# Merge_ESC_Board.net
KiCad netlist of a schematic drawn in Altium Designer
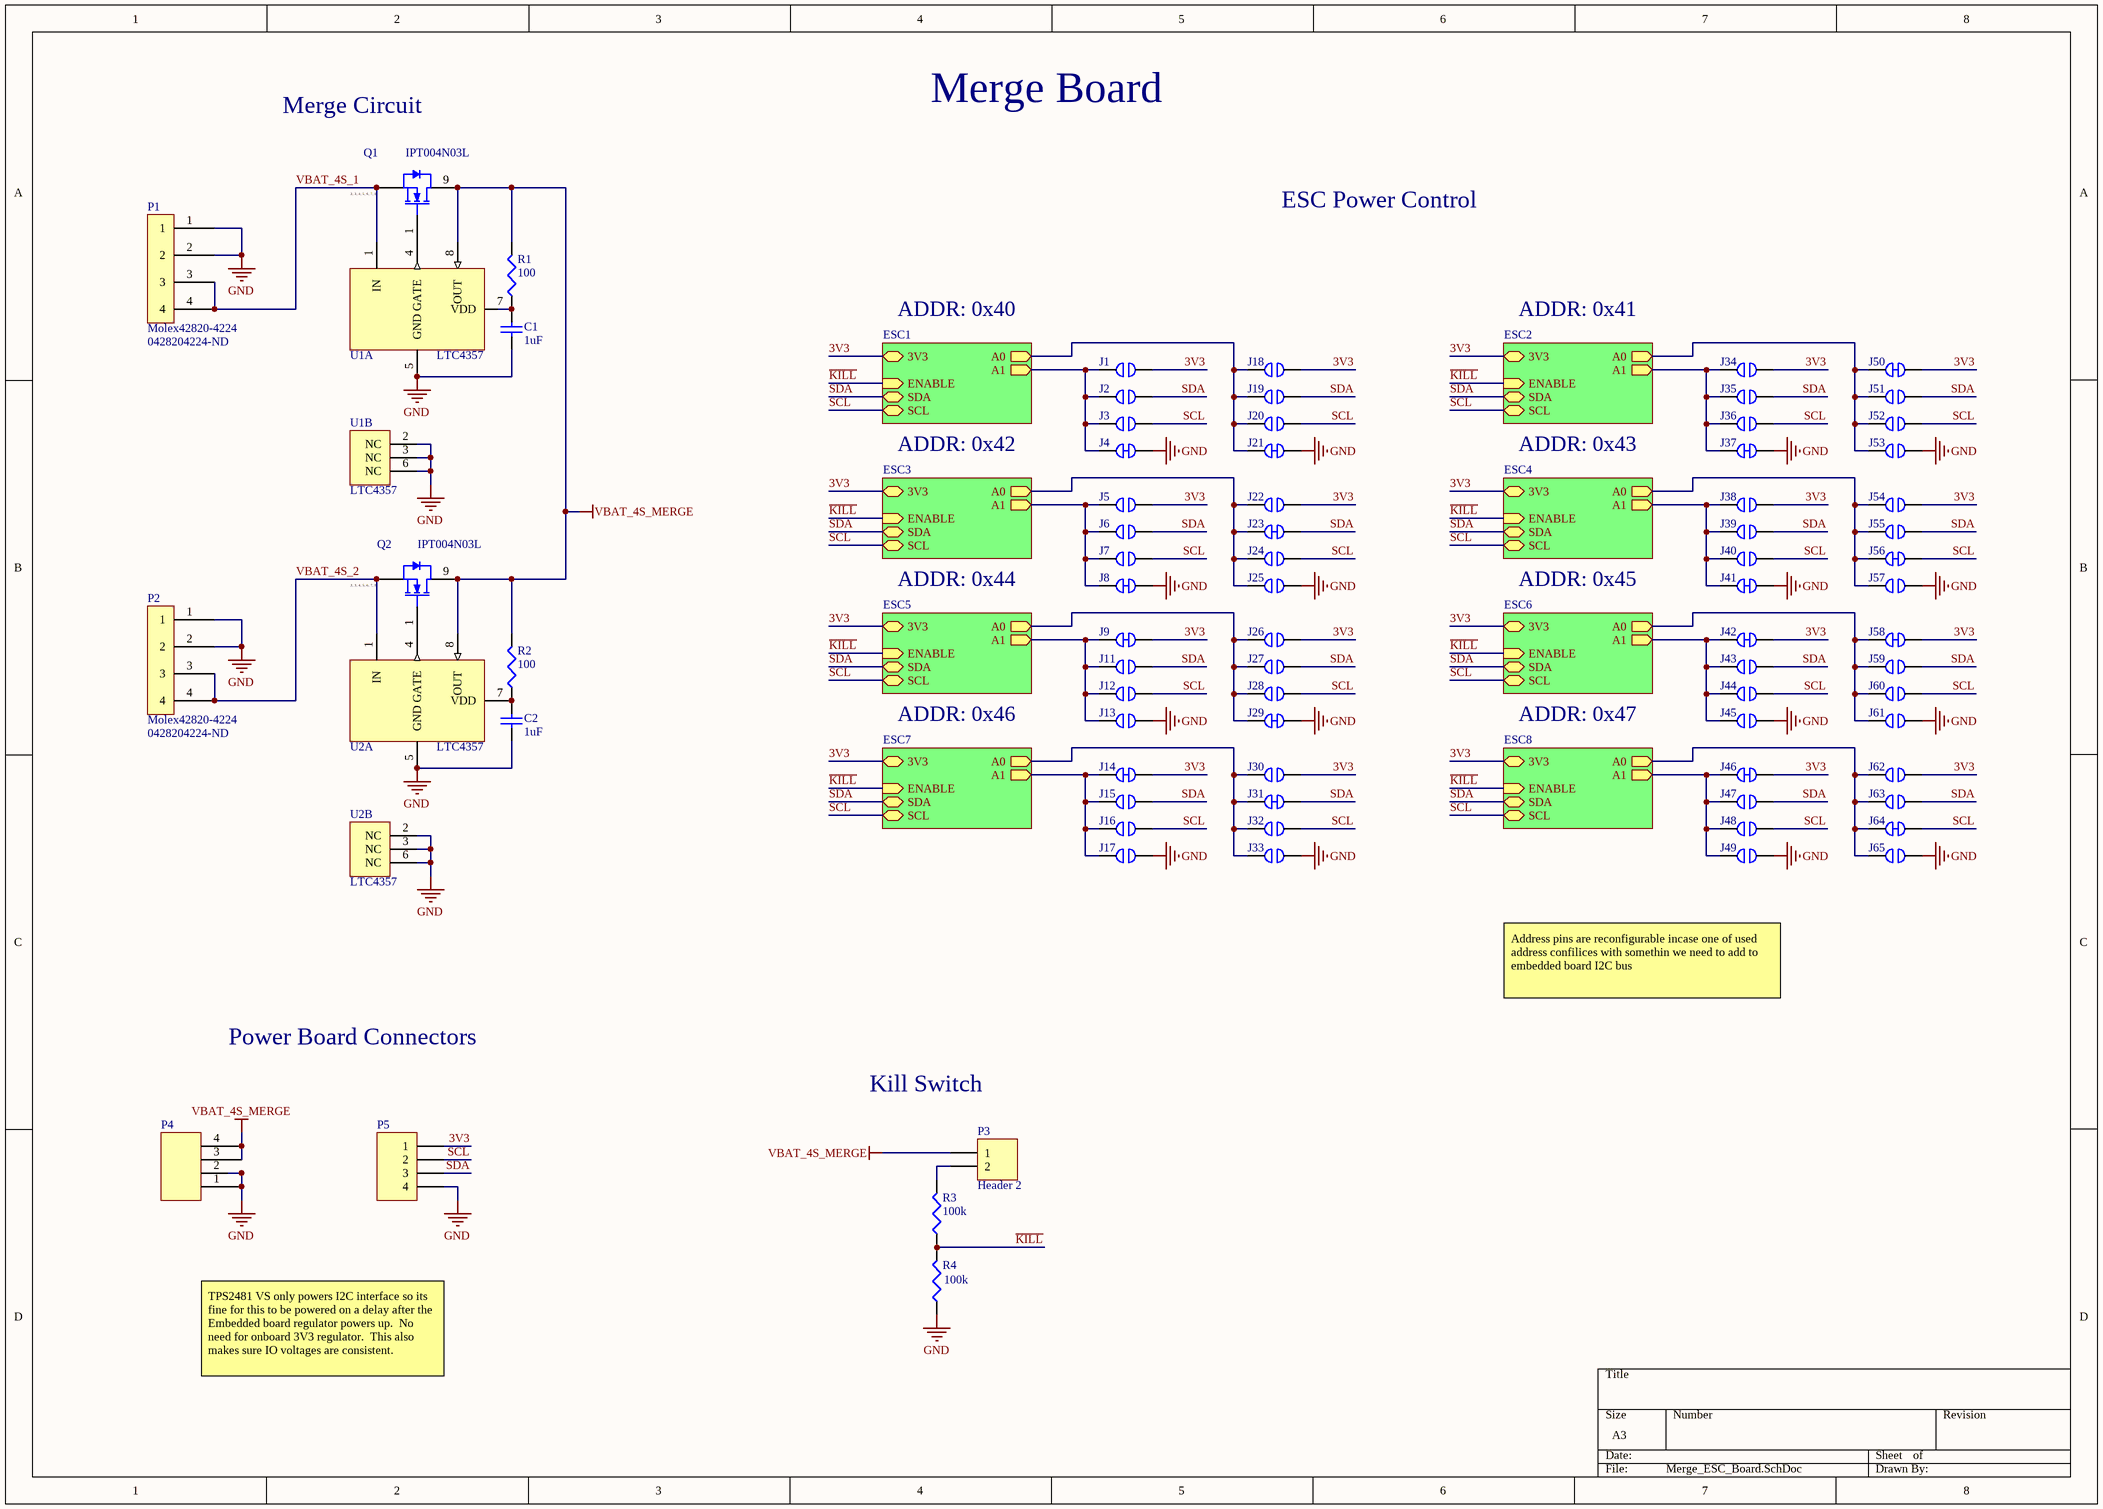
[diagram p0: Merge_ESC_Board.SchDoc]

(export (version "E")
  (design (tool "Eeschema 10.0.6"))
  (components
    (comp (ref "C1")
      (value "1uF")
      (footprint "C1206")
      (description "Capacitor (Semiconductor SIM Model)")
      (fields (field (name "Comment") "Cap Semi") (field (name "PUBLISHER") "Altium Limited"))
      (libsource (lib "Miscellaneous Devices") (part "Cap Semi"))
    )
    (comp (ref "C2")
      (value "1uF")
      (footprint "C1206")
      (description "Capacitor (Semiconductor SIM Model)")
      (fields (field (name "Comment") "Cap Semi") (field (name "PUBLISHER") "Altium Limited"))
      (libsource (lib "Miscellaneous Devices") (part "Cap Semi"))
    )
    (comp (ref "J1")
      (value "JumperOpen")
      (footprint "JUMPER_OPEN")
      (description "Jumper (Default Open)")
      (libsource (lib "Merge_ESC_Board_Library") (part "JumperOpen"))
    )
    (comp (ref "J2")
      (value "JumperOpen")
      (footprint "JUMPER_OPEN")
      (description "Jumper (Default Open)")
      (libsource (lib "Merge_ESC_Board_Library") (part "JumperOpen"))
    )
    (comp (ref "J3")
      (value "JumperOpen")
      (footprint "JUMPER_OPEN")
      (description "Jumper (Default Open)")
      (libsource (lib "Merge_ESC_Board_Library") (part "JumperOpen"))
    )
    (comp (ref "J4")
      (value "JumperShorted")
      (footprint "JUMPER_SHORT")
      (description "Jumper (Default Shorted)")
      (libsource (lib "Merge_ESC_Board_Library") (part "JumperShorted"))
    )
    (comp (ref "J5")
      (value "JumperOpen")
      (footprint "JUMPER_OPEN")
      (description "Jumper (Default Open)")
      (libsource (lib "Merge_ESC_Board_Library") (part "JumperOpen"))
    )
    (comp (ref "J6")
      (value "JumperOpen")
      (footprint "JUMPER_OPEN")
      (description "Jumper (Default Open)")
      (libsource (lib "Merge_ESC_Board_Library") (part "JumperOpen"))
    )
    (comp (ref "J7")
      (value "JumperOpen")
      (footprint "JUMPER_OPEN")
      (description "Jumper (Default Open)")
      (libsource (lib "Merge_ESC_Board_Library") (part "JumperOpen"))
    )
    (comp (ref "J8")
      (value "JumperShorted")
      (footprint "JUMPER_SHORT")
      (description "Jumper (Default Shorted)")
      (libsource (lib "Merge_ESC_Board_Library") (part "JumperShorted"))
    )
    (comp (ref "J9")
      (value "JumperShorted")
      (footprint "JUMPER_SHORT")
      (description "Jumper (Default Shorted)")
      (libsource (lib "Merge_ESC_Board_Library") (part "JumperShorted"))
    )
    (comp (ref "J11")
      (value "JumperOpen")
      (footprint "JUMPER_OPEN")
      (description "Jumper (Default Open)")
      (libsource (lib "Merge_ESC_Board_Library") (part "JumperOpen"))
    )
    (comp (ref "J12")
      (value "JumperOpen")
      (footprint "JUMPER_OPEN")
      (description "Jumper (Default Open)")
      (libsource (lib "Merge_ESC_Board_Library") (part "JumperOpen"))
    )
    (comp (ref "J13")
      (value "JumperOpen")
      (footprint "JUMPER_OPEN")
      (description "Jumper (Default Open)")
      (libsource (lib "Merge_ESC_Board_Library") (part "JumperOpen"))
    )
    (comp (ref "J14")
      (value "JumperShorted")
      (footprint "JUMPER_SHORT")
      (description "Jumper (Default Shorted)")
      (libsource (lib "Merge_ESC_Board_Library") (part "JumperShorted"))
    )
    (comp (ref "J15")
      (value "JumperOpen")
      (footprint "JUMPER_OPEN")
      (description "Jumper (Default Open)")
      (libsource (lib "Merge_ESC_Board_Library") (part "JumperOpen"))
    )
    (comp (ref "J16")
      (value "JumperOpen")
      (footprint "JUMPER_OPEN")
      (description "Jumper (Default Open)")
      (libsource (lib "Merge_ESC_Board_Library") (part "JumperOpen"))
    )
    (comp (ref "J17")
      (value "JumperOpen")
      (footprint "JUMPER_OPEN")
      (description "Jumper (Default Open)")
      (libsource (lib "Merge_ESC_Board_Library") (part "JumperOpen"))
    )
    (comp (ref "J18")
      (value "JumperOpen")
      (footprint "JUMPER_OPEN")
      (description "Jumper (Default Open)")
      (libsource (lib "Merge_ESC_Board_Library") (part "JumperOpen"))
    )
    (comp (ref "J19")
      (value "JumperOpen")
      (footprint "JUMPER_OPEN")
      (description "Jumper (Default Open)")
      (libsource (lib "Merge_ESC_Board_Library") (part "JumperOpen"))
    )
    (comp (ref "J20")
      (value "JumperOpen")
      (footprint "JUMPER_OPEN")
      (description "Jumper (Default Open)")
      (libsource (lib "Merge_ESC_Board_Library") (part "JumperOpen"))
    )
    (comp (ref "J21")
      (value "JumperShorted")
      (footprint "JUMPER_SHORT")
      (description "Jumper (Default Shorted)")
      (libsource (lib "Merge_ESC_Board_Library") (part "JumperShorted"))
    )
    (comp (ref "J22")
      (value "JumperOpen")
      (footprint "JUMPER_OPEN")
      (description "Jumper (Default Open)")
      (libsource (lib "Merge_ESC_Board_Library") (part "JumperOpen"))
    )
    (comp (ref "J23")
      (value "JumperShorted")
      (footprint "JUMPER_SHORT")
      (description "Jumper (Default Shorted)")
      (libsource (lib "Merge_ESC_Board_Library") (part "JumperShorted"))
    )
    (comp (ref "J24")
      (value "JumperOpen")
      (footprint "JUMPER_OPEN")
      (description "Jumper (Default Open)")
      (libsource (lib "Merge_ESC_Board_Library") (part "JumperOpen"))
    )
    (comp (ref "J25")
      (value "JumperOpen")
      (footprint "JUMPER_OPEN")
      (description "Jumper (Default Open)")
      (libsource (lib "Merge_ESC_Board_Library") (part "JumperOpen"))
    )
    (comp (ref "J26")
      (value "JumperOpen")
      (footprint "JUMPER_OPEN")
      (description "Jumper (Default Open)")
      (libsource (lib "Merge_ESC_Board_Library") (part "JumperOpen"))
    )
    (comp (ref "J27")
      (value "JumperOpen")
      (footprint "JUMPER_OPEN")
      (description "Jumper (Default Open)")
      (libsource (lib "Merge_ESC_Board_Library") (part "JumperOpen"))
    )
    (comp (ref "J28")
      (value "JumperOpen")
      (footprint "JUMPER_OPEN")
      (description "Jumper (Default Open)")
      (libsource (lib "Merge_ESC_Board_Library") (part "JumperOpen"))
    )
    (comp (ref "J29")
      (value "JumperShorted")
      (footprint "JUMPER_SHORT")
      (description "Jumper (Default Shorted)")
      (libsource (lib "Merge_ESC_Board_Library") (part "JumperShorted"))
    )
    (comp (ref "J30")
      (value "JumperOpen")
      (footprint "JUMPER_OPEN")
      (description "Jumper (Default Open)")
      (libsource (lib "Merge_ESC_Board_Library") (part "JumperOpen"))
    )
    (comp (ref "J31")
      (value "JumperShorted")
      (footprint "JUMPER_SHORT")
      (description "Jumper (Default Shorted)")
      (libsource (lib "Merge_ESC_Board_Library") (part "JumperShorted"))
    )
    (comp (ref "J32")
      (value "JumperOpen")
      (footprint "JUMPER_OPEN")
      (description "Jumper (Default Open)")
      (libsource (lib "Merge_ESC_Board_Library") (part "JumperOpen"))
    )
    (comp (ref "J33")
      (value "JumperOpen")
      (footprint "JUMPER_OPEN")
      (description "Jumper (Default Open)")
      (libsource (lib "Merge_ESC_Board_Library") (part "JumperOpen"))
    )
    (comp (ref "J34")
      (value "JumperOpen")
      (footprint "JUMPER_OPEN")
      (description "Jumper (Default Open)")
      (libsource (lib "Merge_ESC_Board_Library") (part "JumperOpen"))
    )
    (comp (ref "J35")
      (value "JumperOpen")
      (footprint "JUMPER_OPEN")
      (description "Jumper (Default Open)")
      (libsource (lib "Merge_ESC_Board_Library") (part "JumperOpen"))
    )
    (comp (ref "J36")
      (value "JumperOpen")
      (footprint "JUMPER_OPEN")
      (description "Jumper (Default Open)")
      (libsource (lib "Merge_ESC_Board_Library") (part "JumperOpen"))
    )
    (comp (ref "J37")
      (value "JumperShorted")
      (footprint "JUMPER_SHORT")
      (description "Jumper (Default Shorted)")
      (libsource (lib "Merge_ESC_Board_Library") (part "JumperShorted"))
    )
    (comp (ref "J38")
      (value "JumperOpen")
      (footprint "JUMPER_OPEN")
      (description "Jumper (Default Open)")
      (libsource (lib "Merge_ESC_Board_Library") (part "JumperOpen"))
    )
    (comp (ref "J39")
      (value "JumperOpen")
      (footprint "JUMPER_OPEN")
      (description "Jumper (Default Open)")
      (libsource (lib "Merge_ESC_Board_Library") (part "JumperOpen"))
    )
    (comp (ref "J40")
      (value "JumperOpen")
      (footprint "JUMPER_OPEN")
      (description "Jumper (Default Open)")
      (libsource (lib "Merge_ESC_Board_Library") (part "JumperOpen"))
    )
    (comp (ref "J41")
      (value "JumperShorted")
      (footprint "JUMPER_SHORT")
      (description "Jumper (Default Shorted)")
      (libsource (lib "Merge_ESC_Board_Library") (part "JumperShorted"))
    )
    (comp (ref "J42")
      (value "JumperShorted")
      (footprint "JUMPER_SHORT")
      (description "Jumper (Default Shorted)")
      (libsource (lib "Merge_ESC_Board_Library") (part "JumperShorted"))
    )
    (comp (ref "J43")
      (value "JumperOpen")
      (footprint "JUMPER_OPEN")
      (description "Jumper (Default Open)")
      (libsource (lib "Merge_ESC_Board_Library") (part "JumperOpen"))
    )
    (comp (ref "J44")
      (value "JumperOpen")
      (footprint "JUMPER_OPEN")
      (description "Jumper (Default Open)")
      (libsource (lib "Merge_ESC_Board_Library") (part "JumperOpen"))
    )
    (comp (ref "J45")
      (value "JumperOpen")
      (footprint "JUMPER_OPEN")
      (description "Jumper (Default Open)")
      (libsource (lib "Merge_ESC_Board_Library") (part "JumperOpen"))
    )
    (comp (ref "J46")
      (value "JumperShorted")
      (footprint "JUMPER_SHORT")
      (description "Jumper (Default Shorted)")
      (libsource (lib "Merge_ESC_Board_Library") (part "JumperShorted"))
    )
    (comp (ref "J47")
      (value "JumperOpen")
      (footprint "JUMPER_OPEN")
      (description "Jumper (Default Open)")
      (libsource (lib "Merge_ESC_Board_Library") (part "JumperOpen"))
    )
    (comp (ref "J48")
      (value "JumperOpen")
      (footprint "JUMPER_OPEN")
      (description "Jumper (Default Open)")
      (libsource (lib "Merge_ESC_Board_Library") (part "JumperOpen"))
    )
    (comp (ref "J49")
      (value "JumperOpen")
      (footprint "JUMPER_OPEN")
      (description "Jumper (Default Open)")
      (libsource (lib "Merge_ESC_Board_Library") (part "JumperOpen"))
    )
    (comp (ref "J50")
      (value "JumperShorted")
      (footprint "JUMPER_SHORT")
      (description "Jumper (Default Shorted)")
      (libsource (lib "Merge_ESC_Board_Library") (part "JumperShorted"))
    )
    (comp (ref "J51")
      (value "JumperOpen")
      (footprint "JUMPER_OPEN")
      (description "Jumper (Default Open)")
      (libsource (lib "Merge_ESC_Board_Library") (part "JumperOpen"))
    )
    (comp (ref "J52")
      (value "JumperOpen")
      (footprint "JUMPER_OPEN")
      (description "Jumper (Default Open)")
      (libsource (lib "Merge_ESC_Board_Library") (part "JumperOpen"))
    )
    (comp (ref "J53")
      (value "JumperOpen")
      (footprint "JUMPER_OPEN")
      (description "Jumper (Default Open)")
      (libsource (lib "Merge_ESC_Board_Library") (part "JumperOpen"))
    )
    (comp (ref "J54")
      (value "JumperOpen")
      (footprint "JUMPER_OPEN")
      (description "Jumper (Default Open)")
      (libsource (lib "Merge_ESC_Board_Library") (part "JumperOpen"))
    )
    (comp (ref "J55")
      (value "JumperOpen")
      (footprint "JUMPER_OPEN")
      (description "Jumper (Default Open)")
      (libsource (lib "Merge_ESC_Board_Library") (part "JumperOpen"))
    )
    (comp (ref "J56")
      (value "JumperShorted")
      (footprint "JUMPER_SHORT")
      (description "Jumper (Default Shorted)")
      (libsource (lib "Merge_ESC_Board_Library") (part "JumperShorted"))
    )
    (comp (ref "J57")
      (value "JumperOpen")
      (footprint "JUMPER_OPEN")
      (description "Jumper (Default Open)")
      (libsource (lib "Merge_ESC_Board_Library") (part "JumperOpen"))
    )
    (comp (ref "J58")
      (value "JumperShorted")
      (footprint "JUMPER_SHORT")
      (description "Jumper (Default Shorted)")
      (libsource (lib "Merge_ESC_Board_Library") (part "JumperShorted"))
    )
    (comp (ref "J59")
      (value "JumperOpen")
      (footprint "JUMPER_OPEN")
      (description "Jumper (Default Open)")
      (libsource (lib "Merge_ESC_Board_Library") (part "JumperOpen"))
    )
    (comp (ref "J60")
      (value "JumperOpen")
      (footprint "JUMPER_OPEN")
      (description "Jumper (Default Open)")
      (libsource (lib "Merge_ESC_Board_Library") (part "JumperOpen"))
    )
    (comp (ref "J61")
      (value "JumperOpen")
      (footprint "JUMPER_OPEN")
      (description "Jumper (Default Open)")
      (libsource (lib "Merge_ESC_Board_Library") (part "JumperOpen"))
    )
    (comp (ref "J62")
      (value "JumperOpen")
      (footprint "JUMPER_OPEN")
      (description "Jumper (Default Open)")
      (libsource (lib "Merge_ESC_Board_Library") (part "JumperOpen"))
    )
    (comp (ref "J63")
      (value "JumperOpen")
      (footprint "JUMPER_OPEN")
      (description "Jumper (Default Open)")
      (libsource (lib "Merge_ESC_Board_Library") (part "JumperOpen"))
    )
    (comp (ref "J64")
      (value "JumperShorted")
      (footprint "JUMPER_SHORT")
      (description "Jumper (Default Shorted)")
      (libsource (lib "Merge_ESC_Board_Library") (part "JumperShorted"))
    )
    (comp (ref "J65")
      (value "JumperOpen")
      (footprint "JUMPER_OPEN")
      (description "Jumper (Default Open)")
      (libsource (lib "Merge_ESC_Board_Library") (part "JumperOpen"))
    )
    (comp (ref "P1")
      (value "Molex42820-4224")
      (footprint "Molex42820-4224")
      (fields (field (name "SUPPLIER PART NUMBER 1") "0428204224-ND"))
      (libsource (lib "Merge_ESC_Board_Library") (part "Molex42820-4224"))
    )
    (comp (ref "P2")
      (value "Molex42820-4224")
      (footprint "Molex42820-4224")
      (fields (field (name "SUPPLIER PART NUMBER 1") "0428204224-ND"))
      (libsource (lib "Merge_ESC_Board_Library") (part "Molex42820-4224"))
    )
    (comp (ref "P3")
      (value "Header 2")
      (footprint "HDR1X2")
      (description "Header, 2-Pin")
      (fields (field (name "PUBLISHER") "Altium Limited"))
      (libsource (lib "Miscellaneous Connectors") (part "Header 2"))
    )
    (comp (ref "P4")
      (value "200241-1114")
      (footprint "Molex2002411114")
      (libsource (lib "Merge_ESC_Board_Library") (part "Molex2002411114"))
    )
    (comp (ref "P5")
      (value "Header 4")
      (footprint "DF13-4P-1.25DSA")
      (description "Header, 4-Pin")
      (fields (field (name "PUBLISHER") "Altium Limited"))
      (libsource (lib "Miscellaneous Connectors") (part "Header 4"))
    )
    (comp (ref "Q1")
      (value "IPT004N03L")
      (footprint "INF-PG-HSOF-8-1_V")
      (description "N-Channel OptiMOS(TM) Power-MOSFET, 30 V VDS, 300 A ID, -55 to 175 degC, PG-HSOF-8, Reel, Green")
      (fields (field (name "MANUFACTURER") "Infineon"))
      (libsource (lib "Merge_ESC_Board_Library") (part "IPT004N03L"))
    )
    (comp (ref "Q2")
      (value "IPT004N03L")
      (footprint "INF-PG-HSOF-8-1_V")
      (description "N-Channel OptiMOS(TM) Power-MOSFET, 30 V VDS, 300 A ID, -55 to 175 degC, PG-HSOF-8, Reel, Green")
      (fields (field (name "MANUFACTURER") "Infineon"))
      (libsource (lib "Merge_ESC_Board_Library") (part "IPT004N03L"))
    )
    (comp (ref "R1")
      (value "100")
      (footprint "J1-0603")
      (description "Resistor")
      (fields (field (name "Comment") "Res3") (field (name "PUBLISHER") "Altium Limited"))
      (libsource (lib "Miscellaneous Devices") (part "Res3"))
    )
    (comp (ref "R2")
      (value "100")
      (footprint "J1-0603")
      (description "Resistor")
      (fields (field (name "Comment") "Res3") (field (name "PUBLISHER") "Altium Limited"))
      (libsource (lib "Miscellaneous Devices") (part "Res3"))
    )
    (comp (ref "R3")
      (value "100k")
      (footprint "J1-0603")
      (description "Resistor")
      (fields (field (name "Comment") "Res3") (field (name "PUBLISHER") "Altium Limited"))
      (libsource (lib "Miscellaneous Devices") (part "Res3"))
    )
    (comp (ref "R4")
      (value "100k")
      (footprint "J1-0603")
      (description "Resistor")
      (fields (field (name "Comment") "Res3") (field (name "PUBLISHER") "Altium Limited"))
      (libsource (lib "Miscellaneous Devices") (part "Res3"))
    )
    (comp (ref "U1")
      (value "LTC4357")
      (footprint "LT-MS8-8_N")
      (fields (field (name "MANUFACTURER") "Linear Technology") (field (name "PARTNUMBER") "LTC4357CMS8#PBF"))
      (libsource (lib "Merge_ESC_Board_Library") (part "LTC4357CMS8#PBF"))
    )
    (comp (ref "U2")
      (value "LTC4357")
      (footprint "LT-MS8-8_N")
      (fields (field (name "MANUFACTURER") "Linear Technology") (field (name "PARTNUMBER") "LTC4357CMS8#PBF"))
      (libsource (lib "Merge_ESC_Board_Library") (part "LTC4357CMS8#PBF"))
    )
  )
  (nets
    (net (code "1") (name "/3V3") (class "Default")
      (node (ref "J1") (pin "2") (pinfunction "2_2") (pintype "passive"))
      (node (ref "J14") (pin "2") (pinfunction "2_2") (pintype "passive"))
      (node (ref "J18") (pin "2") (pinfunction "2_2") (pintype "passive"))
      (node (ref "J22") (pin "2") (pinfunction "2_2") (pintype "passive"))
      (node (ref "J26") (pin "2") (pinfunction "2_2") (pintype "passive"))
      (node (ref "J30") (pin "2") (pinfunction "2_2") (pintype "passive"))
      (node (ref "J34") (pin "2") (pinfunction "2_2") (pintype "passive"))
      (node (ref "J38") (pin "2") (pinfunction "2_2") (pintype "passive"))
      (node (ref "J42") (pin "2") (pinfunction "2_2") (pintype "passive"))
      (node (ref "J46") (pin "2") (pinfunction "2_2") (pintype "passive"))
      (node (ref "J5") (pin "2") (pinfunction "2_2") (pintype "passive"))
      (node (ref "J50") (pin "2") (pinfunction "2_2") (pintype "passive"))
      (node (ref "J54") (pin "2") (pinfunction "2_2") (pintype "passive"))
      (node (ref "J58") (pin "2") (pinfunction "2_2") (pintype "passive"))
      (node (ref "J62") (pin "2") (pinfunction "2_2") (pintype "passive"))
      (node (ref "J9") (pin "2") (pinfunction "2_2") (pintype "passive"))
      (node (ref "P5") (pin "1") (pinfunction "1_1") (pintype "passive"))
    )
    (net (code "2") (name "/A0") (class "Default")
      (node (ref "J62") (pin "1") (pinfunction "1_1") (pintype "passive"))
      (node (ref "J63") (pin "1") (pinfunction "1_1") (pintype "passive"))
      (node (ref "J64") (pin "1") (pinfunction "1_1") (pintype "passive"))
      (node (ref "J65") (pin "1") (pinfunction "1_1") (pintype "passive"))
    )
    (net (code "3") (name "/A0_1") (class "Default")
      (node (ref "J50") (pin "1") (pinfunction "1_1") (pintype "passive"))
      (node (ref "J51") (pin "1") (pinfunction "1_1") (pintype "passive"))
      (node (ref "J52") (pin "1") (pinfunction "1_1") (pintype "passive"))
      (node (ref "J53") (pin "1") (pinfunction "1_1") (pintype "passive"))
    )
    (net (code "4") (name "/A0_2") (class "Default")
      (node (ref "J54") (pin "1") (pinfunction "1_1") (pintype "passive"))
      (node (ref "J55") (pin "1") (pinfunction "1_1") (pintype "passive"))
      (node (ref "J56") (pin "1") (pinfunction "1_1") (pintype "passive"))
      (node (ref "J57") (pin "1") (pinfunction "1_1") (pintype "passive"))
    )
    (net (code "5") (name "/A0_3") (class "Default")
      (node (ref "J30") (pin "1") (pinfunction "1_1") (pintype "passive"))
      (node (ref "J31") (pin "1") (pinfunction "1_1") (pintype "passive"))
      (node (ref "J32") (pin "1") (pinfunction "1_1") (pintype "passive"))
      (node (ref "J33") (pin "1") (pinfunction "1_1") (pintype "passive"))
    )
    (net (code "6") (name "/A0_4") (class "Default")
      (node (ref "J26") (pin "1") (pinfunction "1_1") (pintype "passive"))
      (node (ref "J27") (pin "1") (pinfunction "1_1") (pintype "passive"))
      (node (ref "J28") (pin "1") (pinfunction "1_1") (pintype "passive"))
      (node (ref "J29") (pin "1") (pinfunction "1_1") (pintype "passive"))
    )
    (net (code "7") (name "/A0_5") (class "Default")
      (node (ref "J22") (pin "1") (pinfunction "1_1") (pintype "passive"))
      (node (ref "J23") (pin "1") (pinfunction "1_1") (pintype "passive"))
      (node (ref "J24") (pin "1") (pinfunction "1_1") (pintype "passive"))
      (node (ref "J25") (pin "1") (pinfunction "1_1") (pintype "passive"))
    )
    (net (code "8") (name "/A0_6") (class "Default")
      (node (ref "J58") (pin "1") (pinfunction "1_1") (pintype "passive"))
      (node (ref "J59") (pin "1") (pinfunction "1_1") (pintype "passive"))
      (node (ref "J60") (pin "1") (pinfunction "1_1") (pintype "passive"))
      (node (ref "J61") (pin "1") (pinfunction "1_1") (pintype "passive"))
    )
    (net (code "9") (name "/A0_7") (class "Default")
      (node (ref "J18") (pin "1") (pinfunction "1_1") (pintype "passive"))
      (node (ref "J19") (pin "1") (pinfunction "1_1") (pintype "passive"))
      (node (ref "J20") (pin "1") (pinfunction "1_1") (pintype "passive"))
      (node (ref "J21") (pin "1") (pinfunction "1_1") (pintype "passive"))
    )
    (net (code "10") (name "/A1") (class "Default")
      (node (ref "J1") (pin "1") (pinfunction "1_1") (pintype "passive"))
      (node (ref "J2") (pin "1") (pinfunction "1_1") (pintype "passive"))
      (node (ref "J3") (pin "1") (pinfunction "1_1") (pintype "passive"))
      (node (ref "J4") (pin "1") (pinfunction "1_1") (pintype "passive"))
    )
    (net (code "11") (name "/A1_1") (class "Default")
      (node (ref "J34") (pin "1") (pinfunction "1_1") (pintype "passive"))
      (node (ref "J35") (pin "1") (pinfunction "1_1") (pintype "passive"))
      (node (ref "J36") (pin "1") (pinfunction "1_1") (pintype "passive"))
      (node (ref "J37") (pin "1") (pinfunction "1_1") (pintype "passive"))
    )
    (net (code "12") (name "/A1_2") (class "Default")
      (node (ref "J38") (pin "1") (pinfunction "1_1") (pintype "passive"))
      (node (ref "J39") (pin "1") (pinfunction "1_1") (pintype "passive"))
      (node (ref "J40") (pin "1") (pinfunction "1_1") (pintype "passive"))
      (node (ref "J41") (pin "1") (pinfunction "1_1") (pintype "passive"))
    )
    (net (code "13") (name "/A1_3") (class "Default")
      (node (ref "J11") (pin "1") (pinfunction "1_1") (pintype "passive"))
      (node (ref "J12") (pin "1") (pinfunction "1_1") (pintype "passive"))
      (node (ref "J13") (pin "1") (pinfunction "1_1") (pintype "passive"))
      (node (ref "J9") (pin "1") (pinfunction "1_1") (pintype "passive"))
    )
    (net (code "14") (name "/A1_4") (class "Default")
      (node (ref "J14") (pin "1") (pinfunction "1_1") (pintype "passive"))
      (node (ref "J15") (pin "1") (pinfunction "1_1") (pintype "passive"))
      (node (ref "J16") (pin "1") (pinfunction "1_1") (pintype "passive"))
      (node (ref "J17") (pin "1") (pinfunction "1_1") (pintype "passive"))
    )
    (net (code "15") (name "/A1_5") (class "Default")
      (node (ref "J5") (pin "1") (pinfunction "1_1") (pintype "passive"))
      (node (ref "J6") (pin "1") (pinfunction "1_1") (pintype "passive"))
      (node (ref "J7") (pin "1") (pinfunction "1_1") (pintype "passive"))
      (node (ref "J8") (pin "1") (pinfunction "1_1") (pintype "passive"))
    )
    (net (code "16") (name "/A1_6") (class "Default")
      (node (ref "J42") (pin "1") (pinfunction "1_1") (pintype "passive"))
      (node (ref "J43") (pin "1") (pinfunction "1_1") (pintype "passive"))
      (node (ref "J44") (pin "1") (pinfunction "1_1") (pintype "passive"))
      (node (ref "J45") (pin "1") (pinfunction "1_1") (pintype "passive"))
    )
    (net (code "17") (name "/A1_7") (class "Default")
      (node (ref "J46") (pin "1") (pinfunction "1_1") (pintype "passive"))
      (node (ref "J47") (pin "1") (pinfunction "1_1") (pintype "passive"))
      (node (ref "J48") (pin "1") (pinfunction "1_1") (pintype "passive"))
      (node (ref "J49") (pin "1") (pinfunction "1_1") (pintype "passive"))
    )
    (net (code "18") (name "/SCL") (class "Default")
      (node (ref "J12") (pin "2") (pinfunction "2_2") (pintype "passive"))
      (node (ref "J16") (pin "2") (pinfunction "2_2") (pintype "passive"))
      (node (ref "J20") (pin "2") (pinfunction "2_2") (pintype "passive"))
      (node (ref "J24") (pin "2") (pinfunction "2_2") (pintype "passive"))
      (node (ref "J28") (pin "2") (pinfunction "2_2") (pintype "passive"))
      (node (ref "J3") (pin "2") (pinfunction "2_2") (pintype "passive"))
      (node (ref "J32") (pin "2") (pinfunction "2_2") (pintype "passive"))
      (node (ref "J36") (pin "2") (pinfunction "2_2") (pintype "passive"))
      (node (ref "J40") (pin "2") (pinfunction "2_2") (pintype "passive"))
      (node (ref "J44") (pin "2") (pinfunction "2_2") (pintype "passive"))
      (node (ref "J48") (pin "2") (pinfunction "2_2") (pintype "passive"))
      (node (ref "J52") (pin "2") (pinfunction "2_2") (pintype "passive"))
      (node (ref "J56") (pin "2") (pinfunction "2_2") (pintype "passive"))
      (node (ref "J60") (pin "2") (pinfunction "2_2") (pintype "passive"))
      (node (ref "J64") (pin "2") (pinfunction "2_2") (pintype "passive"))
      (node (ref "J7") (pin "2") (pinfunction "2_2") (pintype "passive"))
      (node (ref "P5") (pin "2") (pinfunction "2_2") (pintype "passive"))
    )
    (net (code "19") (name "/SDA") (class "Default")
      (node (ref "J11") (pin "2") (pinfunction "2_2") (pintype "passive"))
      (node (ref "J15") (pin "2") (pinfunction "2_2") (pintype "passive"))
      (node (ref "J19") (pin "2") (pinfunction "2_2") (pintype "passive"))
      (node (ref "J2") (pin "2") (pinfunction "2_2") (pintype "passive"))
      (node (ref "J23") (pin "2") (pinfunction "2_2") (pintype "passive"))
      (node (ref "J27") (pin "2") (pinfunction "2_2") (pintype "passive"))
      (node (ref "J31") (pin "2") (pinfunction "2_2") (pintype "passive"))
      (node (ref "J35") (pin "2") (pinfunction "2_2") (pintype "passive"))
      (node (ref "J39") (pin "2") (pinfunction "2_2") (pintype "passive"))
      (node (ref "J43") (pin "2") (pinfunction "2_2") (pintype "passive"))
      (node (ref "J47") (pin "2") (pinfunction "2_2") (pintype "passive"))
      (node (ref "J51") (pin "2") (pinfunction "2_2") (pintype "passive"))
      (node (ref "J55") (pin "2") (pinfunction "2_2") (pintype "passive"))
      (node (ref "J59") (pin "2") (pinfunction "2_2") (pintype "passive"))
      (node (ref "J6") (pin "2") (pinfunction "2_2") (pintype "passive"))
      (node (ref "J63") (pin "2") (pinfunction "2_2") (pintype "passive"))
      (node (ref "P5") (pin "3") (pinfunction "3_3") (pintype "passive"))
    )
    (net (code "20") (name "/VBAT_4S_1") (class "Default")
      (node (ref "P1") (pin "3") (pinfunction "3_3") (pintype "power_in"))
      (node (ref "P1") (pin "4") (pinfunction "4_4") (pintype "power_in"))
      (node (ref "Q1") (pin "2") (pinfunction "S_2") (pintype "passive"))
      (node (ref "Q1") (pin "3") (pinfunction "S_3") (pintype "passive"))
      (node (ref "Q1") (pin "4") (pinfunction "S_4") (pintype "passive"))
      (node (ref "Q1") (pin "5") (pinfunction "S_5") (pintype "passive"))
      (node (ref "Q1") (pin "6") (pinfunction "S_6") (pintype "passive"))
      (node (ref "Q1") (pin "7") (pinfunction "S_7") (pintype "passive"))
      (node (ref "Q1") (pin "8") (pinfunction "S_8") (pintype "passive"))
      (node (ref "U1") (pin "1") (pinfunction "IN_1") (pintype "power_in"))
    )
    (net (code "21") (name "/VBAT_4S_2") (class "Default")
      (node (ref "P2") (pin "3") (pinfunction "3_3") (pintype "power_in"))
      (node (ref "P2") (pin "4") (pinfunction "4_4") (pintype "power_in"))
      (node (ref "Q2") (pin "2") (pinfunction "S_2") (pintype "passive"))
      (node (ref "Q2") (pin "3") (pinfunction "S_3") (pintype "passive"))
      (node (ref "Q2") (pin "4") (pinfunction "S_4") (pintype "passive"))
      (node (ref "Q2") (pin "5") (pinfunction "S_5") (pintype "passive"))
      (node (ref "Q2") (pin "6") (pinfunction "S_6") (pintype "passive"))
      (node (ref "Q2") (pin "7") (pinfunction "S_7") (pintype "passive"))
      (node (ref "Q2") (pin "8") (pinfunction "S_8") (pintype "passive"))
      (node (ref "U2") (pin "1") (pinfunction "IN_1") (pintype "power_in"))
    )
    (net (code "22") (name "/~{KILL}") (class "Default")
      (node (ref "R3") (pin "1") (pinfunction "1_1") (pintype "passive"))
      (node (ref "R4") (pin "2") (pinfunction "2_2") (pintype "passive"))
    )
    (net (code "23") (name "GND") (class "Default")
      (node (ref "C1") (pin "1") (pinfunction "1_1") (pintype "passive"))
      (node (ref "C2") (pin "1") (pinfunction "1_1") (pintype "passive"))
      (node (ref "J13") (pin "2") (pinfunction "2_2") (pintype "passive"))
      (node (ref "J17") (pin "2") (pinfunction "2_2") (pintype "passive"))
      (node (ref "J21") (pin "2") (pinfunction "2_2") (pintype "passive"))
      (node (ref "J25") (pin "2") (pinfunction "2_2") (pintype "passive"))
      (node (ref "J29") (pin "2") (pinfunction "2_2") (pintype "passive"))
      (node (ref "J33") (pin "2") (pinfunction "2_2") (pintype "passive"))
      (node (ref "J37") (pin "2") (pinfunction "2_2") (pintype "passive"))
      (node (ref "J4") (pin "2") (pinfunction "2_2") (pintype "passive"))
      (node (ref "J41") (pin "2") (pinfunction "2_2") (pintype "passive"))
      (node (ref "J45") (pin "2") (pinfunction "2_2") (pintype "passive"))
      (node (ref "J49") (pin "2") (pinfunction "2_2") (pintype "passive"))
      (node (ref "J53") (pin "2") (pinfunction "2_2") (pintype "passive"))
      (node (ref "J57") (pin "2") (pinfunction "2_2") (pintype "passive"))
      (node (ref "J61") (pin "2") (pinfunction "2_2") (pintype "passive"))
      (node (ref "J65") (pin "2") (pinfunction "2_2") (pintype "passive"))
      (node (ref "J8") (pin "2") (pinfunction "2_2") (pintype "passive"))
      (node (ref "P1") (pin "1") (pinfunction "1_1") (pintype "power_in"))
      (node (ref "P1") (pin "2") (pinfunction "2_2") (pintype "power_in"))
      (node (ref "P2") (pin "1") (pinfunction "1_1") (pintype "power_in"))
      (node (ref "P2") (pin "2") (pinfunction "2_2") (pintype "power_in"))
      (node (ref "P4") (pin "1") (pintype "power_in"))
      (node (ref "P4") (pin "2") (pintype "power_in"))
      (node (ref "P5") (pin "4") (pinfunction "4_4") (pintype "passive"))
      (node (ref "R4") (pin "1") (pinfunction "1_1") (pintype "passive"))
      (node (ref "U1") (pin "2") (pinfunction "NC_2") (pintype "passive"))
      (node (ref "U1") (pin "3") (pinfunction "NC_3") (pintype "passive"))
      (node (ref "U1") (pin "5") (pinfunction "GND_5") (pintype "power_in"))
      (node (ref "U1") (pin "6") (pinfunction "NC_6") (pintype "passive"))
      (node (ref "U2") (pin "2") (pinfunction "NC_2") (pintype "passive"))
      (node (ref "U2") (pin "3") (pinfunction "NC_3") (pintype "passive"))
      (node (ref "U2") (pin "5") (pinfunction "GND_5") (pintype "power_in"))
      (node (ref "U2") (pin "6") (pinfunction "NC_6") (pintype "passive"))
    )
    (net (code "24") (name "Net-(P3-Pad2)") (class "Default")
      (node (ref "P3") (pin "2") (pinfunction "2_2") (pintype "passive"))
      (node (ref "R3") (pin "2") (pinfunction "2_2") (pintype "passive"))
    )
    (net (code "25") (name "Net-(Q1-GATE)") (class "Default")
      (node (ref "Q1") (pin "1") (pinfunction "GATE_1") (pintype "passive"))
      (node (ref "U1") (pin "4") (pinfunction "GATE_4") (pintype "output"))
    )
    (net (code "26") (name "Net-(Q2-GATE)") (class "Default")
      (node (ref "Q2") (pin "1") (pinfunction "GATE_1") (pintype "passive"))
      (node (ref "U2") (pin "4") (pinfunction "GATE_4") (pintype "output"))
    )
    (net (code "27") (name "Net-(U1A-VDD)") (class "Default")
      (node (ref "C1") (pin "2") (pinfunction "2_2") (pintype "passive"))
      (node (ref "R1") (pin "1") (pinfunction "1_1") (pintype "passive"))
      (node (ref "U1") (pin "7") (pinfunction "VDD_7") (pintype "power_in"))
    )
    (net (code "28") (name "Net-(U2A-VDD)") (class "Default")
      (node (ref "C2") (pin "2") (pinfunction "2_2") (pintype "passive"))
      (node (ref "R2") (pin "1") (pinfunction "1_1") (pintype "passive"))
      (node (ref "U2") (pin "7") (pinfunction "VDD_7") (pintype "power_in"))
    )
    (net (code "29") (name "VBAT_4S_MERGE") (class "Default")
      (node (ref "P3") (pin "1") (pinfunction "1_1") (pintype "passive"))
      (node (ref "P4") (pin "3") (pintype "power_in"))
      (node (ref "P4") (pin "4") (pintype "power_in"))
      (node (ref "Q1") (pin "9") (pinfunction "D_9") (pintype "passive"))
      (node (ref "Q2") (pin "9") (pinfunction "D_9") (pintype "passive"))
      (node (ref "R1") (pin "2") (pinfunction "2_2") (pintype "passive"))
      (node (ref "R2") (pin "2") (pinfunction "2_2") (pintype "passive"))
      (node (ref "U1") (pin "8") (pinfunction "OUT_8") (pintype "input"))
      (node (ref "U2") (pin "8") (pinfunction "OUT_8") (pintype "input"))
    )
  )
)
